# outgoing_connection.net
KiCad netlist of a schematic drawn in Altium Designer
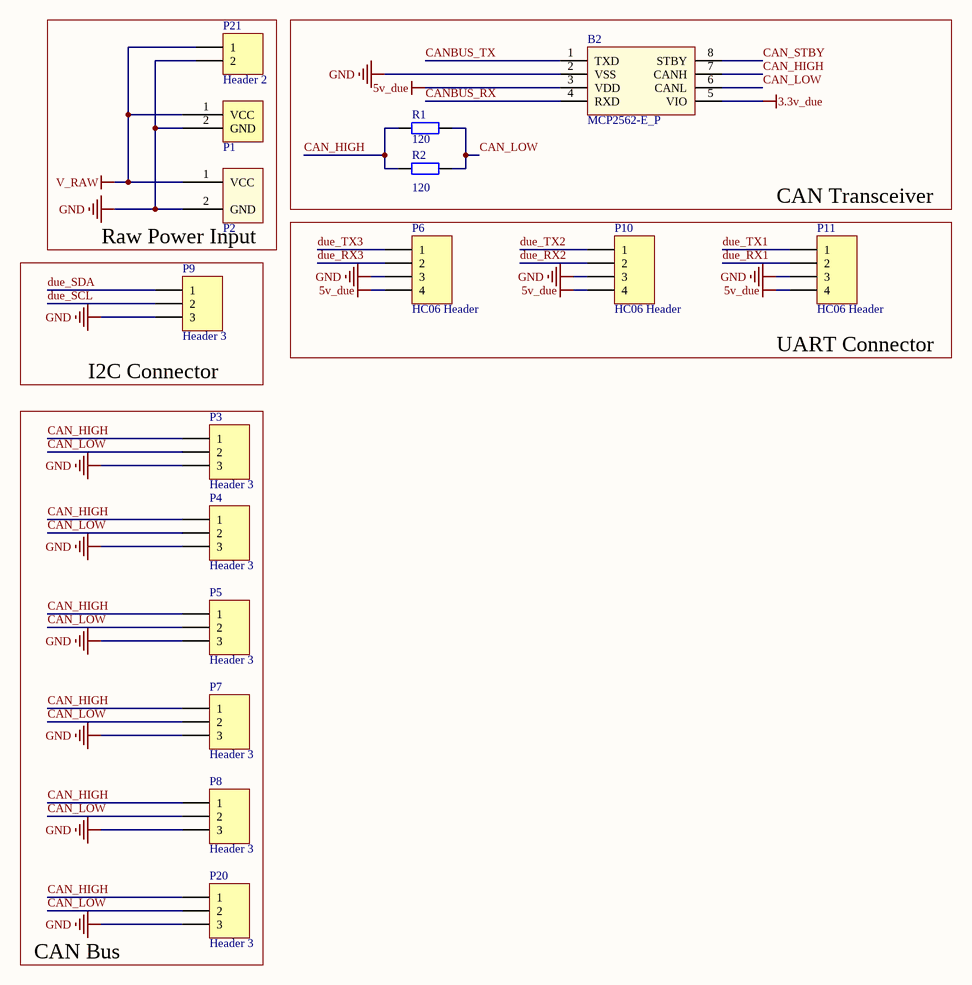
[diagram p0: outgoing connection.SchDoc]

(export (version "E")
  (design (tool "Eeschema 10.0.6"))
  (components
    (comp (ref "B2")
      (value "MCP2562-E_P")
      (footprint "DIP781W56P254L950H533Q8N")
      (fields
        (field (name "RS PART NUMBER") "7990225")
        (field (name "MANUFACTURER_PART_NUMBER") "MCP2562-E/P")
      )
      (libsource (lib "MCP2562-E_P") (part "MCP2562-E_P"))
    )
    (comp (ref "P1")
      (value "5557 Connector")
      (footprint "5557_connector")
      (libsource (lib "5557 connector") (part "5557_connector"))
    )
    (comp (ref "P2")
      (value "big Pin power port")
      (footprint "bigPin_power_port")
      (libsource (lib "bigPin_power_port") (part "big Pin power port"))
    )
    (comp (ref "P3")
      (value "Header 3")
      (footprint "HDR1X3")
      (description "Header, 3-Pin")
      (fields (field (name "PUBLISHER") "Altium Limited"))
      (libsource (lib "Miscellaneous Connectors") (part "Header 3"))
    )
    (comp (ref "P4")
      (value "Header 3")
      (footprint "HDR1X3")
      (description "Header, 3-Pin")
      (fields (field (name "PUBLISHER") "Altium Limited"))
      (libsource (lib "Miscellaneous Connectors") (part "Header 3"))
    )
    (comp (ref "P5")
      (value "Header 3")
      (footprint "HDR1X3")
      (description "Header, 3-Pin")
      (fields (field (name "PUBLISHER") "Altium Limited"))
      (libsource (lib "Miscellaneous Connectors") (part "Header 3"))
    )
    (comp (ref "P6")
      (value "HC06 Header")
      (footprint "HDR1X4")
      (description "Header, 4-Pin")
      (fields (field (name "PUBLISHER") "Altium Limited"))
      (libsource (lib "Miscellaneous Connectors") (part "Header 4"))
    )
    (comp (ref "P7")
      (value "Header 3")
      (footprint "HDR1X3")
      (description "Header, 3-Pin")
      (fields (field (name "PUBLISHER") "Altium Limited"))
      (libsource (lib "Miscellaneous Connectors") (part "Header 3"))
    )
    (comp (ref "P8")
      (value "Header 3")
      (footprint "HDR1X3")
      (description "Header, 3-Pin")
      (fields (field (name "PUBLISHER") "Altium Limited"))
      (libsource (lib "Miscellaneous Connectors") (part "Header 3"))
    )
    (comp (ref "P9")
      (value "Header 3")
      (footprint "HDR1X3")
      (description "Header, 3-Pin")
      (fields (field (name "PUBLISHER") "Altium Limited"))
      (libsource (lib "Miscellaneous Connectors") (part "Header 3"))
    )
    (comp (ref "P10")
      (value "HC06 Header")
      (footprint "HDR1X4")
      (description "Header, 4-Pin")
      (fields (field (name "PUBLISHER") "Altium Limited"))
      (libsource (lib "Miscellaneous Connectors") (part "Header 4"))
    )
    (comp (ref "P11")
      (value "HC06 Header")
      (footprint "HDR1X4")
      (description "Header, 4-Pin")
      (fields (field (name "PUBLISHER") "Altium Limited"))
      (libsource (lib "Miscellaneous Connectors") (part "Header 4"))
    )
    (comp (ref "P20")
      (value "Header 3")
      (footprint "HDR1X3")
      (description "Header, 3-Pin")
      (fields (field (name "PUBLISHER") "Altium Limited"))
      (libsource (lib "Miscellaneous Connectors") (part "Header 3"))
    )
    (comp (ref "P21")
      (value "Header 2")
      (footprint "HDR1X2")
      (description "Header, 2-Pin")
      (fields (field (name "PUBLISHER") "Altium Limited"))
      (libsource (lib "Miscellaneous Connectors") (part "Header 2"))
    )
    (comp (ref "R1")
      (value "120")
      (footprint "AXIAL-0.4")
      (description "Resistor")
      (fields (field (name "Comment") "Res2") (field (name "PUBLISHER") "Altium Limited"))
      (libsource (lib "Miscellaneous Devices") (part "Res2"))
    )
    (comp (ref "R2")
      (value "120")
      (footprint "AXIAL-0.4")
      (description "Resistor")
      (fields (field (name "Comment") "Res2") (field (name "PUBLISHER") "Altium Limited"))
      (libsource (lib "Miscellaneous Devices") (part "Res2"))
    )
  )
  (nets
    (net (code "1") (name "/CANBUS_RX") (class "Default")
      (node (ref "B2") (pin "4") (pinfunction "RXD_4") (pintype "passive"))
    )
    (net (code "2") (name "/CANBUS_TX") (class "Default")
      (node (ref "B2") (pin "1") (pinfunction "TXD_1") (pintype "passive"))
    )
    (net (code "3") (name "/CAN_HIGH") (class "Default")
      (node (ref "B2") (pin "7") (pinfunction "CANH_7") (pintype "passive"))
      (node (ref "P20") (pin "1") (pinfunction "1_1") (pintype "passive"))
      (node (ref "P3") (pin "1") (pinfunction "1_1") (pintype "passive"))
      (node (ref "P4") (pin "1") (pinfunction "1_1") (pintype "passive"))
      (node (ref "P5") (pin "1") (pinfunction "1_1") (pintype "passive"))
      (node (ref "P7") (pin "1") (pinfunction "1_1") (pintype "passive"))
      (node (ref "P8") (pin "1") (pinfunction "1_1") (pintype "passive"))
      (node (ref "R1") (pin "1") (pinfunction "1_1") (pintype "passive"))
      (node (ref "R2") (pin "1") (pinfunction "1_1") (pintype "passive"))
    )
    (net (code "4") (name "/CAN_LOW") (class "Default")
      (node (ref "B2") (pin "6") (pinfunction "CANL_6") (pintype "passive"))
      (node (ref "P20") (pin "2") (pinfunction "2_2") (pintype "passive"))
      (node (ref "P3") (pin "2") (pinfunction "2_2") (pintype "passive"))
      (node (ref "P4") (pin "2") (pinfunction "2_2") (pintype "passive"))
      (node (ref "P5") (pin "2") (pinfunction "2_2") (pintype "passive"))
      (node (ref "P7") (pin "2") (pinfunction "2_2") (pintype "passive"))
      (node (ref "P8") (pin "2") (pinfunction "2_2") (pintype "passive"))
      (node (ref "R1") (pin "2") (pinfunction "2_2") (pintype "passive"))
      (node (ref "R2") (pin "2") (pinfunction "2_2") (pintype "passive"))
    )
    (net (code "5") (name "/CAN_STBY") (class "Default")
      (node (ref "B2") (pin "8") (pinfunction "STBY_8") (pintype "passive"))
    )
    (net (code "6") (name "/due_RX1") (class "Default")
      (node (ref "P11") (pin "2") (pinfunction "2_2") (pintype "passive"))
    )
    (net (code "7") (name "/due_RX2") (class "Default")
      (node (ref "P10") (pin "2") (pinfunction "2_2") (pintype "passive"))
    )
    (net (code "8") (name "/due_RX3") (class "Default")
      (node (ref "P6") (pin "2") (pinfunction "2_2") (pintype "passive"))
    )
    (net (code "9") (name "/due_SCL") (class "Default")
      (node (ref "P9") (pin "2") (pinfunction "2_2") (pintype "passive"))
    )
    (net (code "10") (name "/due_SDA") (class "Default")
      (node (ref "P9") (pin "1") (pinfunction "1_1") (pintype "passive"))
    )
    (net (code "11") (name "/due_TX1") (class "Default")
      (node (ref "P11") (pin "1") (pinfunction "1_1") (pintype "passive"))
    )
    (net (code "12") (name "/due_TX2") (class "Default")
      (node (ref "P10") (pin "1") (pinfunction "1_1") (pintype "passive"))
    )
    (net (code "13") (name "/due_TX3") (class "Default")
      (node (ref "P6") (pin "1") (pinfunction "1_1") (pintype "passive"))
    )
    (net (code "14") (name "3.3v_due") (class "Default")
      (node (ref "B2") (pin "5") (pinfunction "VIO_5") (pintype "passive"))
    )
    (net (code "15") (name "5v_due") (class "Default")
      (node (ref "B2") (pin "3") (pinfunction "VDD_3") (pintype "passive"))
      (node (ref "P10") (pin "4") (pinfunction "4_4") (pintype "passive"))
      (node (ref "P11") (pin "4") (pinfunction "4_4") (pintype "passive"))
      (node (ref "P6") (pin "4") (pinfunction "4_4") (pintype "passive"))
    )
    (net (code "16") (name "GND") (class "Default")
      (node (ref "B2") (pin "2") (pinfunction "VSS_2") (pintype "passive"))
      (node (ref "P1") (pin "2") (pinfunction "GND_2") (pintype "passive"))
      (node (ref "P10") (pin "3") (pinfunction "3_3") (pintype "passive"))
      (node (ref "P11") (pin "3") (pinfunction "3_3") (pintype "passive"))
      (node (ref "P2") (pin "2") (pinfunction "GND_2") (pintype "passive"))
      (node (ref "P20") (pin "3") (pinfunction "3_3") (pintype "passive"))
      (node (ref "P21") (pin "2") (pinfunction "2_2") (pintype "passive"))
      (node (ref "P3") (pin "3") (pinfunction "3_3") (pintype "passive"))
      (node (ref "P4") (pin "3") (pinfunction "3_3") (pintype "passive"))
      (node (ref "P5") (pin "3") (pinfunction "3_3") (pintype "passive"))
      (node (ref "P6") (pin "3") (pinfunction "3_3") (pintype "passive"))
      (node (ref "P7") (pin "3") (pinfunction "3_3") (pintype "passive"))
      (node (ref "P8") (pin "3") (pinfunction "3_3") (pintype "passive"))
      (node (ref "P9") (pin "3") (pinfunction "3_3") (pintype "passive"))
    )
    (net (code "17") (name "V_RAW") (class "Default")
      (node (ref "P1") (pin "1") (pinfunction "VCC_1") (pintype "passive"))
      (node (ref "P2") (pin "1") (pinfunction "VCC_1") (pintype "passive"))
      (node (ref "P21") (pin "1") (pinfunction "1_1") (pintype "passive"))
    )
  )
)
